# wch554g.net
KiCad netlist of a schematic drawn in Altium Designer
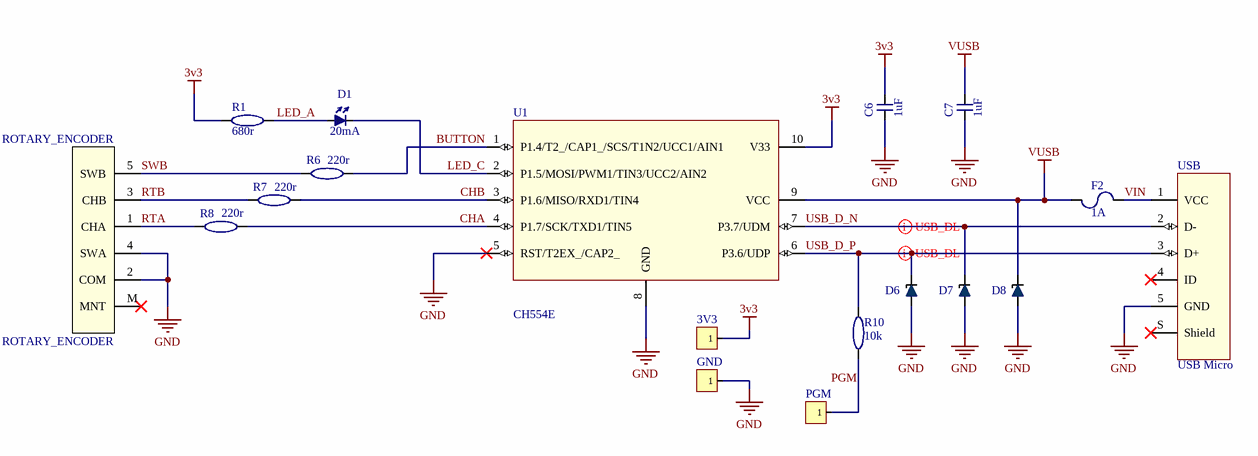
[diagram p0: wch554g.SchDoc]

(export (version "E")
  (design (tool "Eeschema 10.0.6"))
  (components
    (comp (ref "3V3") (value "CON2") (footprint "CON2") (libsource (lib "wch554e") (part "CON2")))
    (comp (ref "C6")
      (value "1uF")
      (footprint "MLCC_0603")
      (description "MLCC")
      (fields (field (name "JLCPCB PART #") "C29936"))
      (libsource (lib "wch554e") (part "CAP_CERAMIC"))
    )
    (comp (ref "C7")
      (value "1uF")
      (footprint "MLCC_0603")
      (description "MLCC")
      (fields (field (name "JLCPCB PART #") "C29936"))
      (libsource (lib "wch554e") (part "CAP_CERAMIC"))
    )
    (comp (ref "D1")
      (value "20mA")
      (footprint "SMT_LED_0603")
      (description "LED")
      (fields (field (name "JLCPCB PART #") "C205445"))
      (libsource (lib "wch554e") (part "LED"))
    )
    (comp (ref "D6")
      (value "TVS_DIODE")
      (footprint "TVS_DIODE")
      (description "TVS Diode")
      (fields (field (name "JLCPCB PART #") "C151980"))
      (libsource (lib "wch554e") (part "TVS_DIODE"))
    )
    (comp (ref "D7")
      (value "TVS_DIODE")
      (footprint "TVS_DIODE")
      (description "TVS Diode")
      (fields (field (name "JLCPCB PART #") "C151980"))
      (libsource (lib "wch554e") (part "TVS_DIODE"))
    )
    (comp (ref "D8")
      (value "TVS_DIODE")
      (footprint "TVS_DIODE")
      (description "TVS Diode")
      (fields (field (name "JLCPCB PART #") "C151980"))
      (libsource (lib "wch554e") (part "TVS_DIODE"))
    )
    (comp (ref "F2")
      (value "1A")
      (footprint "FUSE 0603")
      (description "Resettable fuse")
      (fields (field (name "JLCPCB PART #") "C210357"))
      (libsource (lib "wch554e") (part "FUSE"))
    )
    (comp (ref "GND") (value "CON2") (footprint "CON2") (libsource (lib "wch554e") (part "CON2")))
    (comp (ref "PGM") (value "CON2") (footprint "CON2") (libsource (lib "wch554e") (part "CON2")))
    (comp (ref "R1")
      (value "680r")
      (footprint "SMT_RES_0603")
      (description "Resistor")
      (fields (field (name "JLCPCB PART #") "C23228"))
      (libsource (lib "wch554e") (part "RESISTOR"))
    )
    (comp (ref "R6")
      (value "220r")
      (footprint "SMT_RES_0603")
      (description "Resistor")
      (fields (field (name "JLCPCB PART #") "C27592"))
      (libsource (lib "wch554e") (part "RESISTOR"))
    )
    (comp (ref "R7")
      (value "220r")
      (footprint "SMT_RES_0603")
      (description "Resistor")
      (fields (field (name "JLCPCB PART #") "C27592"))
      (libsource (lib "wch554e") (part "RESISTOR"))
    )
    (comp (ref "R8")
      (value "220r")
      (footprint "SMT_RES_0603")
      (description "Resistor")
      (fields (field (name "JLCPCB PART #") "C27592"))
      (libsource (lib "wch554e") (part "RESISTOR"))
    )
    (comp (ref "R10")
      (value "10k")
      (footprint "SMT_RES_0603")
      (description "Resistor")
      (fields (field (name "JLCPCB PART #") "C25804"))
      (libsource (lib "") (part "RESISTOR_1"))
    )
    (comp (ref "ROTARY_ENCODER")
      (value "ROTARY_ENCODER")
      (footprint "ENCODER")
      (description "Rotary Encoder")
      (libsource (lib "wch554e") (part "ROTARY_ENCODER"))
    )
    (comp (ref "U1")
      (value "CH554E")
      (footprint "MSOP10")
      (fields (field (name "JLCPCB PART #") "C111293"))
      (libsource (lib "wch554e") (part "CH554E"))
    )
    (comp (ref "USB")
      (value "USB Micro")
      (footprint "USB MICRO B")
      (description "USB Receptacle")
      (fields (field (name "JLCPCB PART #") "C397452"))
      (libsource (lib "wch554e") (part "USB_SOCKET"))
    )
  )
  (nets
    (net (code "1") (name "/BUTTON") (class "Default")
      (node (ref "R6") (pin "2") (pinfunction "B_2") (pintype "passive"))
      (node (ref "U1") (pin "1") (pinfunction "P1.4/T2_/CAP1_/SCS/T1N2/UCC1/AIN1_1") (pintype "bidirectional"))
    )
    (net (code "2") (name "/CHA") (class "Default")
      (node (ref "R8") (pin "2") (pinfunction "B_2") (pintype "passive"))
      (node (ref "U1") (pin "4") (pinfunction "P1.7/SCK/TXD1/TIN5_4") (pintype "bidirectional"))
    )
    (net (code "3") (name "/CHB") (class "Default")
      (node (ref "R7") (pin "2") (pinfunction "B_2") (pintype "passive"))
      (node (ref "U1") (pin "3") (pinfunction "P1.6/MISO/RXD1/TIN4_3") (pintype "bidirectional"))
    )
    (net (code "4") (name "/LED_A") (class "Default")
      (node (ref "D1") (pin "2") (pinfunction "A_2") (pintype "passive"))
      (node (ref "R1") (pin "2") (pinfunction "B_2") (pintype "passive"))
    )
    (net (code "5") (name "/LED_C") (class "Default")
      (node (ref "D1") (pin "1") (pinfunction "K_1") (pintype "passive"))
      (node (ref "U1") (pin "2") (pinfunction "P1.5/MOSI/PWM1/TIN3/UCC2/AIN2_2") (pintype "bidirectional"))
    )
    (net (code "6") (name "/PGM") (class "Default")
      (node (ref "PGM") (pin "1") (pinfunction "1_1") (pintype "passive"))
      (node (ref "R10") (pin "1") (pinfunction "A_1") (pintype "passive"))
    )
    (net (code "7") (name "/RTA") (class "Default")
      (node (ref "R8") (pin "1") (pinfunction "A_1") (pintype "passive"))
      (node (ref "ROTARY_ENCODER") (pin "1") (pinfunction "CHA_1") (pintype "passive"))
    )
    (net (code "8") (name "/RTB") (class "Default")
      (node (ref "R7") (pin "1") (pinfunction "A_1") (pintype "passive"))
      (node (ref "ROTARY_ENCODER") (pin "3") (pinfunction "CHB_3") (pintype "passive"))
    )
    (net (code "9") (name "/SWB") (class "Default")
      (node (ref "R6") (pin "1") (pinfunction "A_1") (pintype "passive"))
      (node (ref "ROTARY_ENCODER") (pin "5") (pinfunction "SWB_5") (pintype "passive"))
    )
    (net (code "10") (name "/USB_D_N") (class "Default")
      (node (ref "D7") (pin "1") (pinfunction "K_1") (pintype "passive"))
      (node (ref "U1") (pin "7") (pinfunction "P3.7/UDM_7") (pintype "bidirectional"))
      (node (ref "USB") (pin "2") (pinfunction "D-_2") (pintype "bidirectional"))
    )
    (net (code "11") (name "/USB_D_P") (class "Default")
      (node (ref "D6") (pin "1") (pinfunction "K_1") (pintype "passive"))
      (node (ref "R10") (pin "2") (pinfunction "B_2") (pintype "passive"))
      (node (ref "U1") (pin "6") (pinfunction "P3.6/UDP_6") (pintype "bidirectional"))
      (node (ref "USB") (pin "3") (pinfunction "D+_3") (pintype "bidirectional"))
    )
    (net (code "12") (name "/VIN") (class "Default")
      (node (ref "F2") (pin "1") (pinfunction "1_1") (pintype "power_in"))
      (node (ref "USB") (pin "1") (pinfunction "VCC_1") (pintype "passive"))
    )
    (net (code "13") (name "3v3") (class "Default")
      (node (ref "3V3") (pin "1") (pinfunction "1_1") (pintype "passive"))
      (node (ref "C6") (pin "2") (pinfunction "B_2") (pintype "passive"))
      (node (ref "R1") (pin "1") (pinfunction "A_1") (pintype "passive"))
      (node (ref "U1") (pin "10") (pinfunction "V33_10") (pintype "power_in"))
    )
    (net (code "14") (name "GND") (class "Default")
      (node (ref "C6") (pin "1") (pinfunction "A_1") (pintype "passive"))
      (node (ref "C7") (pin "1") (pinfunction "A_1") (pintype "passive"))
      (node (ref "D6") (pin "2") (pinfunction "A_2") (pintype "passive"))
      (node (ref "D7") (pin "2") (pinfunction "A_2") (pintype "passive"))
      (node (ref "D8") (pin "2") (pinfunction "A_2") (pintype "passive"))
      (node (ref "GND") (pin "1") (pinfunction "1_1") (pintype "passive"))
      (node (ref "ROTARY_ENCODER") (pin "2") (pinfunction "COM_2") (pintype "passive"))
      (node (ref "ROTARY_ENCODER") (pin "4") (pinfunction "SWA_4") (pintype "passive"))
      (node (ref "U1") (pin "5") (pinfunction "RST/T2EX_/CAP2__5") (pintype "bidirectional"))
      (node (ref "U1") (pin "8") (pinfunction "GND_8") (pintype "power_in"))
      (node (ref "USB") (pin "5") (pinfunction "GND_5") (pintype "passive"))
    )
    (net (code "15") (name "VUSB") (class "Default")
      (node (ref "C7") (pin "2") (pinfunction "B_2") (pintype "passive"))
      (node (ref "D8") (pin "1") (pinfunction "K_1") (pintype "passive"))
      (node (ref "F2") (pin "2") (pinfunction "2_2") (pintype "power_in"))
      (node (ref "U1") (pin "9") (pinfunction "VCC_9") (pintype "power_in"))
    )
    (net (code "16") (name "unconnected-(ROTARY_ENCODER-MNT-PadM)") (class "Default")
      (node (ref "ROTARY_ENCODER") (pin "M") (pinfunction "MNT_M") (pintype "passive+no_connect"))
    )
    (net (code "17") (name "unconnected-(USB-ID-Pad4)") (class "Default")
      (node (ref "USB") (pin "4") (pinfunction "ID_4") (pintype "passive+no_connect"))
    )
    (net (code "18") (name "unconnected-(USB-Shield-PadS)") (class "Default")
      (node (ref "USB") (pin "S") (pinfunction "Shield_S") (pintype "passive+no_connect"))
    )
  )
)
